# ESP_Module_No_Battery.net
KiCad netlist of a schematic drawn in EAGLE
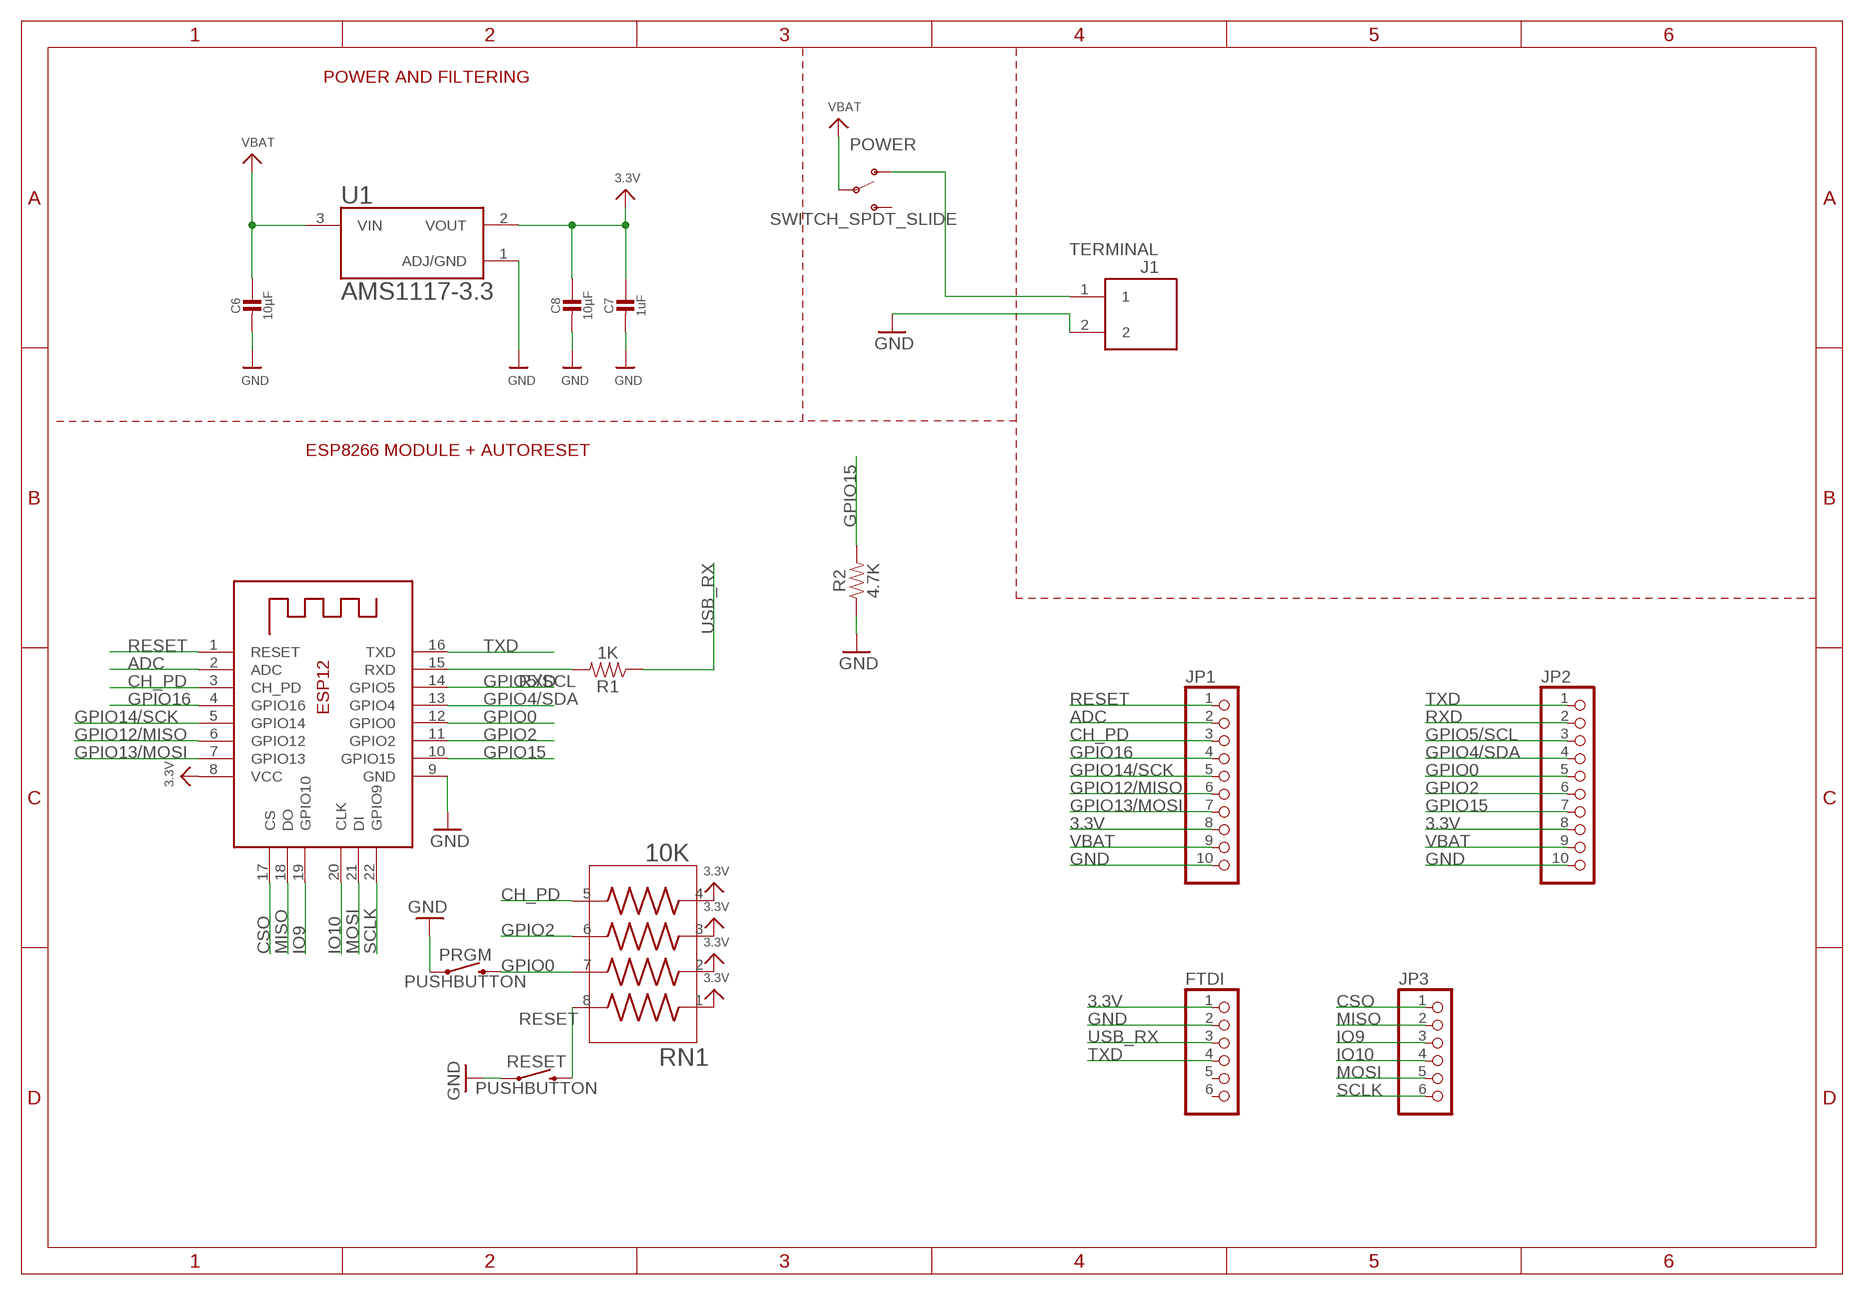
[diagram p0: schematic, sheet 1]

(export (version "E")
  (design (tool "Eeschema 10.0.6"))
  (components
    (comp (ref "C6")
      (value "10µF")
      (footprint "eagle-import:0805-NO")
      (libsource (lib "eagle-import") (part "CAP_CERAMIC0805-NOOUTLINE"))
    )
    (comp (ref "C7")
      (value "1uF")
      (footprint "eagle-import:0603-NO")
      (libsource (lib "eagle-import") (part "CAP_CERAMIC0603_NO"))
    )
    (comp (ref "C8")
      (value "10µF")
      (footprint "eagle-import:0805-NO")
      (libsource (lib "eagle-import") (part "CAP_CERAMIC0805-NOOUTLINE"))
    )
    (comp (ref "FTDI")
      (value "PINHD-1X6")
      (footprint "eagle-import:1X06")
      (libsource (lib "eagle-import") (part "PINHD-1X6"))
    )
    (comp (ref "J1")
      (value "TERMINAL")
      (footprint "eagle-import:ED555_2DS")
      (libsource (lib "eagle-import") (part "TERMINAL"))
    )
    (comp (ref "JP1")
      (value "PINHD-1X10")
      (footprint "eagle-import:1X10")
      (libsource (lib "eagle-import") (part "PINHD-1X10"))
    )
    (comp (ref "JP2")
      (value "PINHD-1X10")
      (footprint "eagle-import:1X10")
      (libsource (lib "eagle-import") (part "PINHD-1X10"))
    )
    (comp (ref "JP3")
      (value "PINHD-1X6")
      (footprint "eagle-import:1X06")
      (libsource (lib "eagle-import") (part "PINHD-1X6"))
    )
    (comp (ref "POWER")
      (value "SWITCH_SPDT_SLIDE")
      (footprint "eagle-import:SWITCH_SPDT_PTH_11.6X4.0MM")
      (libsource (lib "eagle-import") (part "SWITCH_SPDT_SLIDE"))
    )
    (comp (ref "PRGM")
      (value "PUSHBUTTON")
      (footprint "eagle-import:TACTILE_SWITCH_SMD_6.0X3.5MM")
      (libsource (lib "eagle-import") (part "PUSHBUTTON"))
    )
    (comp (ref "R1")
      (value "1K")
      (footprint "eagle-import:1206")
      (libsource (lib "eagle-import") (part "RESISTOR1206"))
    )
    (comp (ref "R2")
      (value "4.7K")
      (footprint "eagle-import:1206")
      (libsource (lib "eagle-import") (part "RESISTOR1206"))
    )
    (comp (ref "RESET")
      (value "PUSHBUTTON")
      (footprint "eagle-import:TACTILE_SWITCH_SMD_6.0X3.5MM")
      (libsource (lib "eagle-import") (part "PUSHBUTTON"))
    )
    (comp (ref "RN1")
      (value "10K")
      (footprint "eagle-import:RESCAF80P320X160X60-8N")
      (fields (field (name "MF") "Bourns") (field (name "MP") "CAY16-750J4LF"))
      (libsource (lib "eagle-import") (part "CAY16-750J4LF"))
    )
    (comp (ref "U1")
      (value "AMS1117-3.3")
      (footprint "eagle-import:SOT229P700X180-4N")
      (fields (field (name "MF") "Advanced Monolithic Systems"))
      (libsource (lib "eagle-import") (part "AMS1117-3.3"))
    )
    (comp (ref "X2")
      (value "ESP-12")
      (footprint "eagle-import:ESP-12E")
      (libsource (lib "eagle-import") (part "ESP-12E"))
    )
  )
  (nets
    (net (code "1") (name "/ADC") (class "Default")
      (node (ref "JP1") (pin "2") (pinfunction "2_2") (pintype "passive"))
      (node (ref "X2") (pin "2") (pinfunction "ADC_2") (pintype "passive"))
    )
    (net (code "2") (name "/CH_PD") (class "Default")
      (node (ref "JP1") (pin "3") (pinfunction "3_3") (pintype "passive"))
      (node (ref "RN1") (pin "5") (pinfunction "5_5") (pintype "passive"))
      (node (ref "X2") (pin "3") (pinfunction "CH_PD_3") (pintype "input"))
    )
    (net (code "3") (name "/CSO") (class "Default")
      (node (ref "JP3") (pin "1") (pinfunction "1_1") (pintype "passive"))
      (node (ref "X2") (pin "17") (pinfunction "CS_17") (pintype "bidirectional"))
    )
    (net (code "4") (name "/GPIO0") (class "Default")
      (node (ref "JP2") (pin "5") (pinfunction "5_5") (pintype "passive"))
      (node (ref "PRGM") (pin "2") (pinfunction "2_2") (pintype "passive"))
      (node (ref "RN1") (pin "7") (pinfunction "7_7") (pintype "passive"))
      (node (ref "X2") (pin "12") (pinfunction "GPIO0_12") (pintype "bidirectional"))
    )
    (net (code "5") (name "/GPIO2") (class "Default")
      (node (ref "JP2") (pin "6") (pinfunction "6_6") (pintype "passive"))
      (node (ref "RN1") (pin "6") (pinfunction "6_6") (pintype "passive"))
      (node (ref "X2") (pin "11") (pinfunction "GPIO2_11") (pintype "bidirectional"))
    )
    (net (code "6") (name "/GPIO4{slash}SDA") (class "Default")
      (node (ref "JP2") (pin "4") (pinfunction "4_4") (pintype "passive"))
      (node (ref "X2") (pin "13") (pinfunction "GPIO4_13") (pintype "bidirectional"))
    )
    (net (code "7") (name "/GPIO5{slash}SCL") (class "Default")
      (node (ref "JP2") (pin "3") (pinfunction "3_3") (pintype "passive"))
      (node (ref "X2") (pin "14") (pinfunction "GPIO5_14") (pintype "bidirectional"))
    )
    (net (code "8") (name "/GPIO12{slash}MISO") (class "Default")
      (node (ref "JP1") (pin "6") (pinfunction "6_6") (pintype "passive"))
      (node (ref "X2") (pin "6") (pinfunction "GPIO12_6") (pintype "bidirectional"))
    )
    (net (code "9") (name "/GPIO13{slash}MOSI") (class "Default")
      (node (ref "JP1") (pin "7") (pinfunction "7_7") (pintype "passive"))
      (node (ref "X2") (pin "7") (pinfunction "GPIO13_7") (pintype "bidirectional"))
    )
    (net (code "10") (name "/GPIO14{slash}SCK") (class "Default")
      (node (ref "JP1") (pin "5") (pinfunction "5_5") (pintype "passive"))
      (node (ref "X2") (pin "5") (pinfunction "GPIO14_5") (pintype "bidirectional"))
    )
    (net (code "11") (name "/GPIO15") (class "Default")
      (node (ref "JP2") (pin "7") (pinfunction "7_7") (pintype "passive"))
      (node (ref "R2") (pin "2") (pinfunction "2_2") (pintype "passive"))
      (node (ref "X2") (pin "10") (pinfunction "GPIO15_10") (pintype "bidirectional"))
    )
    (net (code "12") (name "/GPIO16") (class "Default")
      (node (ref "JP1") (pin "4") (pinfunction "4_4") (pintype "passive"))
      (node (ref "X2") (pin "4") (pinfunction "GPIO16_4") (pintype "bidirectional"))
    )
    (net (code "13") (name "/IO9") (class "Default")
      (node (ref "JP3") (pin "3") (pinfunction "3_3") (pintype "passive"))
      (node (ref "X2") (pin "19") (pinfunction "GPIO10_19") (pintype "bidirectional"))
    )
    (net (code "14") (name "/IO10") (class "Default")
      (node (ref "JP3") (pin "4") (pinfunction "4_4") (pintype "passive"))
      (node (ref "X2") (pin "20") (pinfunction "CLK_20") (pintype "bidirectional"))
    )
    (net (code "15") (name "/MISO") (class "Default")
      (node (ref "JP3") (pin "2") (pinfunction "2_2") (pintype "passive"))
      (node (ref "X2") (pin "18") (pinfunction "DO_18") (pintype "bidirectional"))
    )
    (net (code "16") (name "/MOSI") (class "Default")
      (node (ref "JP3") (pin "5") (pinfunction "5_5") (pintype "passive"))
      (node (ref "X2") (pin "21") (pinfunction "DI_21") (pintype "bidirectional"))
    )
    (net (code "17") (name "/RESET") (class "Default")
      (node (ref "JP1") (pin "1") (pinfunction "1_1") (pintype "passive"))
      (node (ref "RESET") (pin "2") (pinfunction "2_2") (pintype "passive"))
      (node (ref "RN1") (pin "8") (pinfunction "8_8") (pintype "passive"))
      (node (ref "X2") (pin "1") (pinfunction "RESET_1") (pintype "input"))
    )
    (net (code "18") (name "/RXD") (class "Default")
      (node (ref "JP2") (pin "2") (pinfunction "2_2") (pintype "passive"))
      (node (ref "R1") (pin "2") (pinfunction "2_2") (pintype "passive"))
      (node (ref "X2") (pin "15") (pinfunction "RXD_15") (pintype "input"))
    )
    (net (code "19") (name "/SCLK") (class "Default")
      (node (ref "JP3") (pin "6") (pinfunction "6_6") (pintype "passive"))
      (node (ref "X2") (pin "22") (pinfunction "GPIO9_22") (pintype "bidirectional"))
    )
    (net (code "20") (name "/TXD") (class "Default")
      (node (ref "FTDI") (pin "4") (pinfunction "4_4") (pintype "passive"))
      (node (ref "JP2") (pin "1") (pinfunction "1_1") (pintype "passive"))
      (node (ref "X2") (pin "16") (pinfunction "TXD_16") (pintype "output"))
    )
    (net (code "21") (name "/USB_RX") (class "Default")
      (node (ref "FTDI") (pin "3") (pinfunction "3_3") (pintype "passive"))
      (node (ref "R1") (pin "1") (pinfunction "1_1") (pintype "passive"))
    )
    (net (code "22") (name "3.3V") (class "Default")
      (node (ref "C7") (pin "1") (pinfunction "1_1") (pintype "passive"))
      (node (ref "C8") (pin "1") (pinfunction "1_1") (pintype "passive"))
      (node (ref "FTDI") (pin "1") (pinfunction "1_1") (pintype "passive"))
      (node (ref "JP1") (pin "8") (pinfunction "8_8") (pintype "passive"))
      (node (ref "JP2") (pin "8") (pinfunction "8_8") (pintype "passive"))
      (node (ref "RN1") (pin "1") (pinfunction "1_1") (pintype "passive"))
      (node (ref "RN1") (pin "2") (pinfunction "2_2") (pintype "passive"))
      (node (ref "RN1") (pin "3") (pinfunction "3_3") (pintype "passive"))
      (node (ref "RN1") (pin "4") (pinfunction "4_4") (pintype "passive"))
      (node (ref "U1") (pin "2") (pinfunction "VOUT_2") (pintype "output"))
      (node (ref "X2") (pin "8") (pinfunction "VCC_8") (pintype "power_in"))
    )
    (net (code "23") (name "GND") (class "Default")
      (node (ref "C6") (pin "2") (pinfunction "2_2") (pintype "passive"))
      (node (ref "C7") (pin "2") (pinfunction "2_2") (pintype "passive"))
      (node (ref "C8") (pin "2") (pinfunction "2_2") (pintype "passive"))
      (node (ref "FTDI") (pin "2") (pinfunction "2_2") (pintype "passive"))
      (node (ref "J1") (pin "2") (pinfunction "2_2") (pintype "bidirectional"))
      (node (ref "JP1") (pin "10") (pinfunction "10_10") (pintype "passive"))
      (node (ref "JP2") (pin "10") (pinfunction "10_10") (pintype "passive"))
      (node (ref "PRGM") (pin "1") (pinfunction "1_1") (pintype "passive"))
      (node (ref "R2") (pin "1") (pinfunction "1_1") (pintype "passive"))
      (node (ref "RESET") (pin "1") (pinfunction "1_1") (pintype "passive"))
      (node (ref "U1") (pin "1") (pinfunction "ADJ/GND_1") (pintype "power_in"))
      (node (ref "X2") (pin "9") (pinfunction "GND_9") (pintype "power_in"))
    )
    (net (code "24") (name "Net-(POWER-O)") (class "Default")
      (node (ref "J1") (pin "1") (pinfunction "1_1") (pintype "bidirectional"))
      (node (ref "POWER") (pin "1") (pinfunction "O_1") (pintype "passive"))
    )
    (net (code "25") (name "VBAT") (class "Default")
      (node (ref "C6") (pin "1") (pinfunction "1_1") (pintype "passive"))
      (node (ref "JP1") (pin "9") (pinfunction "9_9") (pintype "passive"))
      (node (ref "JP2") (pin "9") (pinfunction "9_9") (pintype "passive"))
      (node (ref "POWER") (pin "2") (pinfunction "P_2") (pintype "passive"))
      (node (ref "U1") (pin "3") (pinfunction "VIN_3") (pintype "input"))
    )
    (net (code "26") (name "unconnected-(FTDI-Pad5)") (class "Default")
      (node (ref "FTDI") (pin "5") (pinfunction "5_5") (pintype "passive"))
    )
    (net (code "27") (name "unconnected-(FTDI-Pad6)") (class "Default")
      (node (ref "FTDI") (pin "6") (pinfunction "6_6") (pintype "passive"))
    )
    (net (code "28") (name "unconnected-(POWER-S-Pad3)") (class "Default")
      (node (ref "POWER") (pin "3") (pinfunction "S_3") (pintype "passive"))
    )
  )
)
